# DoorBellBothRelayBJT.net
KiCad netlist of a schematic drawn in EAGLE
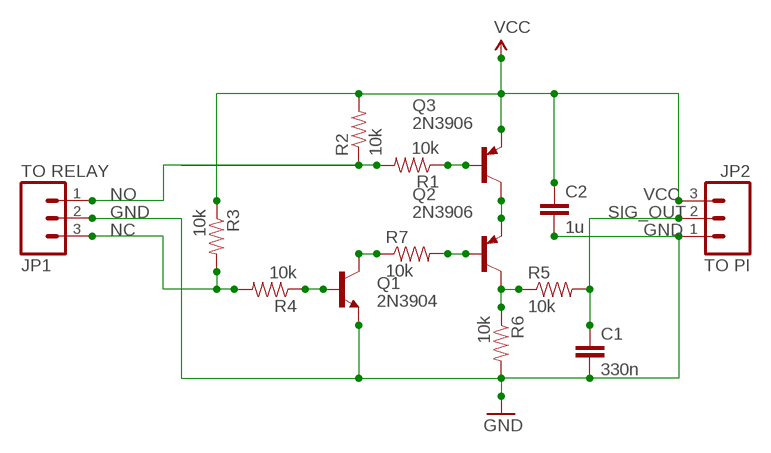
[diagram p0: schematic, sheet 1]

(export (version "E")
  (design (tool "Eeschema 10.0.6"))
  (components
    (comp (ref "C1")
      (value "330n")
      (footprint "eagle-import:CAP-PTH-SMALL-KIT")
      (libsource (lib "eagle-import") (part "CAPKIT"))
    )
    (comp (ref "C2")
      (value "1u")
      (footprint "eagle-import:CAP-PTH-SMALL-KIT")
      (libsource (lib "eagle-import") (part "CAPKIT"))
    )
    (comp (ref "JP1")
      (value "TO RELAY")
      (footprint "eagle-import:1X03_NO_SILK")
      (libsource (lib "eagle-import") (part "M031X03_NO_SILK"))
    )
    (comp (ref "JP2")
      (value "TO PI")
      (footprint "eagle-import:1X03_NO_SILK")
      (libsource (lib "eagle-import") (part "M031X03_NO_SILK"))
    )
    (comp (ref "Q1")
      (value "2N3904")
      (footprint "eagle-import:TO-92")
      (libsource (lib "eagle-import") (part "TRANSISTOR_NPN2N3904"))
    )
    (comp (ref "Q2")
      (value "2N3906")
      (footprint "eagle-import:TO92")
      (libsource (lib "eagle-import") (part "2N3906"))
    )
    (comp (ref "Q3")
      (value "2N3906")
      (footprint "eagle-import:TO92")
      (libsource (lib "eagle-import") (part "2N3906"))
    )
    (comp (ref "R1")
      (value "10k")
      (footprint "eagle-import:AXIAL-0.3EZ")
      (libsource (lib "eagle-import") (part "RESISTOREZ"))
    )
    (comp (ref "R2")
      (value "10k")
      (footprint "eagle-import:AXIAL-0.3EZ")
      (libsource (lib "eagle-import") (part "RESISTOREZ"))
    )
    (comp (ref "R3")
      (value "10k")
      (footprint "eagle-import:AXIAL-0.3EZ")
      (libsource (lib "eagle-import") (part "RESISTOREZ"))
    )
    (comp (ref "R4")
      (value "10k")
      (footprint "eagle-import:AXIAL-0.3EZ")
      (libsource (lib "eagle-import") (part "RESISTOREZ"))
    )
    (comp (ref "R5")
      (value "10k")
      (footprint "eagle-import:AXIAL-0.3EZ")
      (libsource (lib "eagle-import") (part "RESISTOREZ"))
    )
    (comp (ref "R6")
      (value "10k")
      (footprint "eagle-import:AXIAL-0.3EZ")
      (libsource (lib "eagle-import") (part "RESISTOREZ"))
    )
    (comp (ref "R7")
      (value "10k")
      (footprint "eagle-import:AXIAL-0.3EZ")
      (libsource (lib "eagle-import") (part "RESISTOREZ"))
    )
  )
  (nets
    (net (code "1") (name "/NC") (class "Default")
      (node (ref "JP1") (pin "3") (pinfunction "3_3") (pintype "passive"))
      (node (ref "R3") (pin "P$2") (pinfunction "2_P$2") (pintype "passive"))
      (node (ref "R4") (pin "P$2") (pinfunction "2_P$2") (pintype "passive"))
    )
    (net (code "2") (name "/NO") (class "Default")
      (node (ref "JP1") (pin "1") (pinfunction "1_1") (pintype "passive"))
      (node (ref "R1") (pin "P$2") (pinfunction "2_P$2") (pintype "passive"))
      (node (ref "R2") (pin "P$1") (pinfunction "1_P$1") (pintype "passive"))
    )
    (net (code "3") (name "/SIG_OUT") (class "Default")
      (node (ref "C1") (pin "1") (pinfunction "1_1") (pintype "passive"))
      (node (ref "JP2") (pin "2") (pinfunction "2_2") (pintype "passive"))
      (node (ref "R5") (pin "P$2") (pinfunction "2_P$2") (pintype "passive"))
    )
    (net (code "4") (name "GND") (class "Default")
      (node (ref "C1") (pin "2") (pinfunction "2_2") (pintype "passive"))
      (node (ref "C2") (pin "2") (pinfunction "2_2") (pintype "passive"))
      (node (ref "JP1") (pin "2") (pinfunction "2_2") (pintype "passive"))
      (node (ref "JP2") (pin "1") (pinfunction "1_1") (pintype "passive"))
      (node (ref "Q1") (pin "1") (pinfunction "E_1") (pintype "passive"))
      (node (ref "R6") (pin "P$2") (pinfunction "2_P$2") (pintype "passive"))
    )
    (net (code "5") (name "Net-(Q1-B)") (class "Default")
      (node (ref "Q1") (pin "2") (pinfunction "B_2") (pintype "passive"))
      (node (ref "R4") (pin "P$1") (pinfunction "1_P$1") (pintype "passive"))
    )
    (net (code "6") (name "Net-(Q1-C)") (class "Default")
      (node (ref "Q1") (pin "3") (pinfunction "C_3") (pintype "passive"))
      (node (ref "R7") (pin "P$1") (pinfunction "1_P$1") (pintype "passive"))
    )
    (net (code "7") (name "Net-(Q2-B)") (class "Default")
      (node (ref "Q2") (pin "2") (pinfunction "B_2") (pintype "passive"))
      (node (ref "R7") (pin "P$2") (pinfunction "2_P$2") (pintype "passive"))
    )
    (net (code "8") (name "Net-(Q2-C)") (class "Default")
      (node (ref "Q2") (pin "1") (pinfunction "C_1") (pintype "passive"))
      (node (ref "R5") (pin "P$1") (pinfunction "1_P$1") (pintype "passive"))
      (node (ref "R6") (pin "P$1") (pinfunction "1_P$1") (pintype "passive"))
    )
    (net (code "9") (name "Net-(Q2-E)") (class "Default")
      (node (ref "Q2") (pin "3") (pinfunction "E_3") (pintype "passive"))
      (node (ref "Q3") (pin "1") (pinfunction "C_1") (pintype "passive"))
    )
    (net (code "10") (name "Net-(Q3-B)") (class "Default")
      (node (ref "Q3") (pin "2") (pinfunction "B_2") (pintype "passive"))
      (node (ref "R1") (pin "P$1") (pinfunction "1_P$1") (pintype "passive"))
    )
    (net (code "11") (name "VCC") (class "Default")
      (node (ref "C2") (pin "1") (pinfunction "1_1") (pintype "passive"))
      (node (ref "JP2") (pin "3") (pinfunction "3_3") (pintype "passive"))
      (node (ref "Q3") (pin "3") (pinfunction "E_3") (pintype "passive"))
      (node (ref "R2") (pin "P$2") (pinfunction "2_P$2") (pintype "passive"))
      (node (ref "R3") (pin "P$1") (pinfunction "1_P$1") (pintype "passive"))
    )
  )
)
